# KickerBoard6B.net
KiCad netlist of a schematic drawn in EAGLE
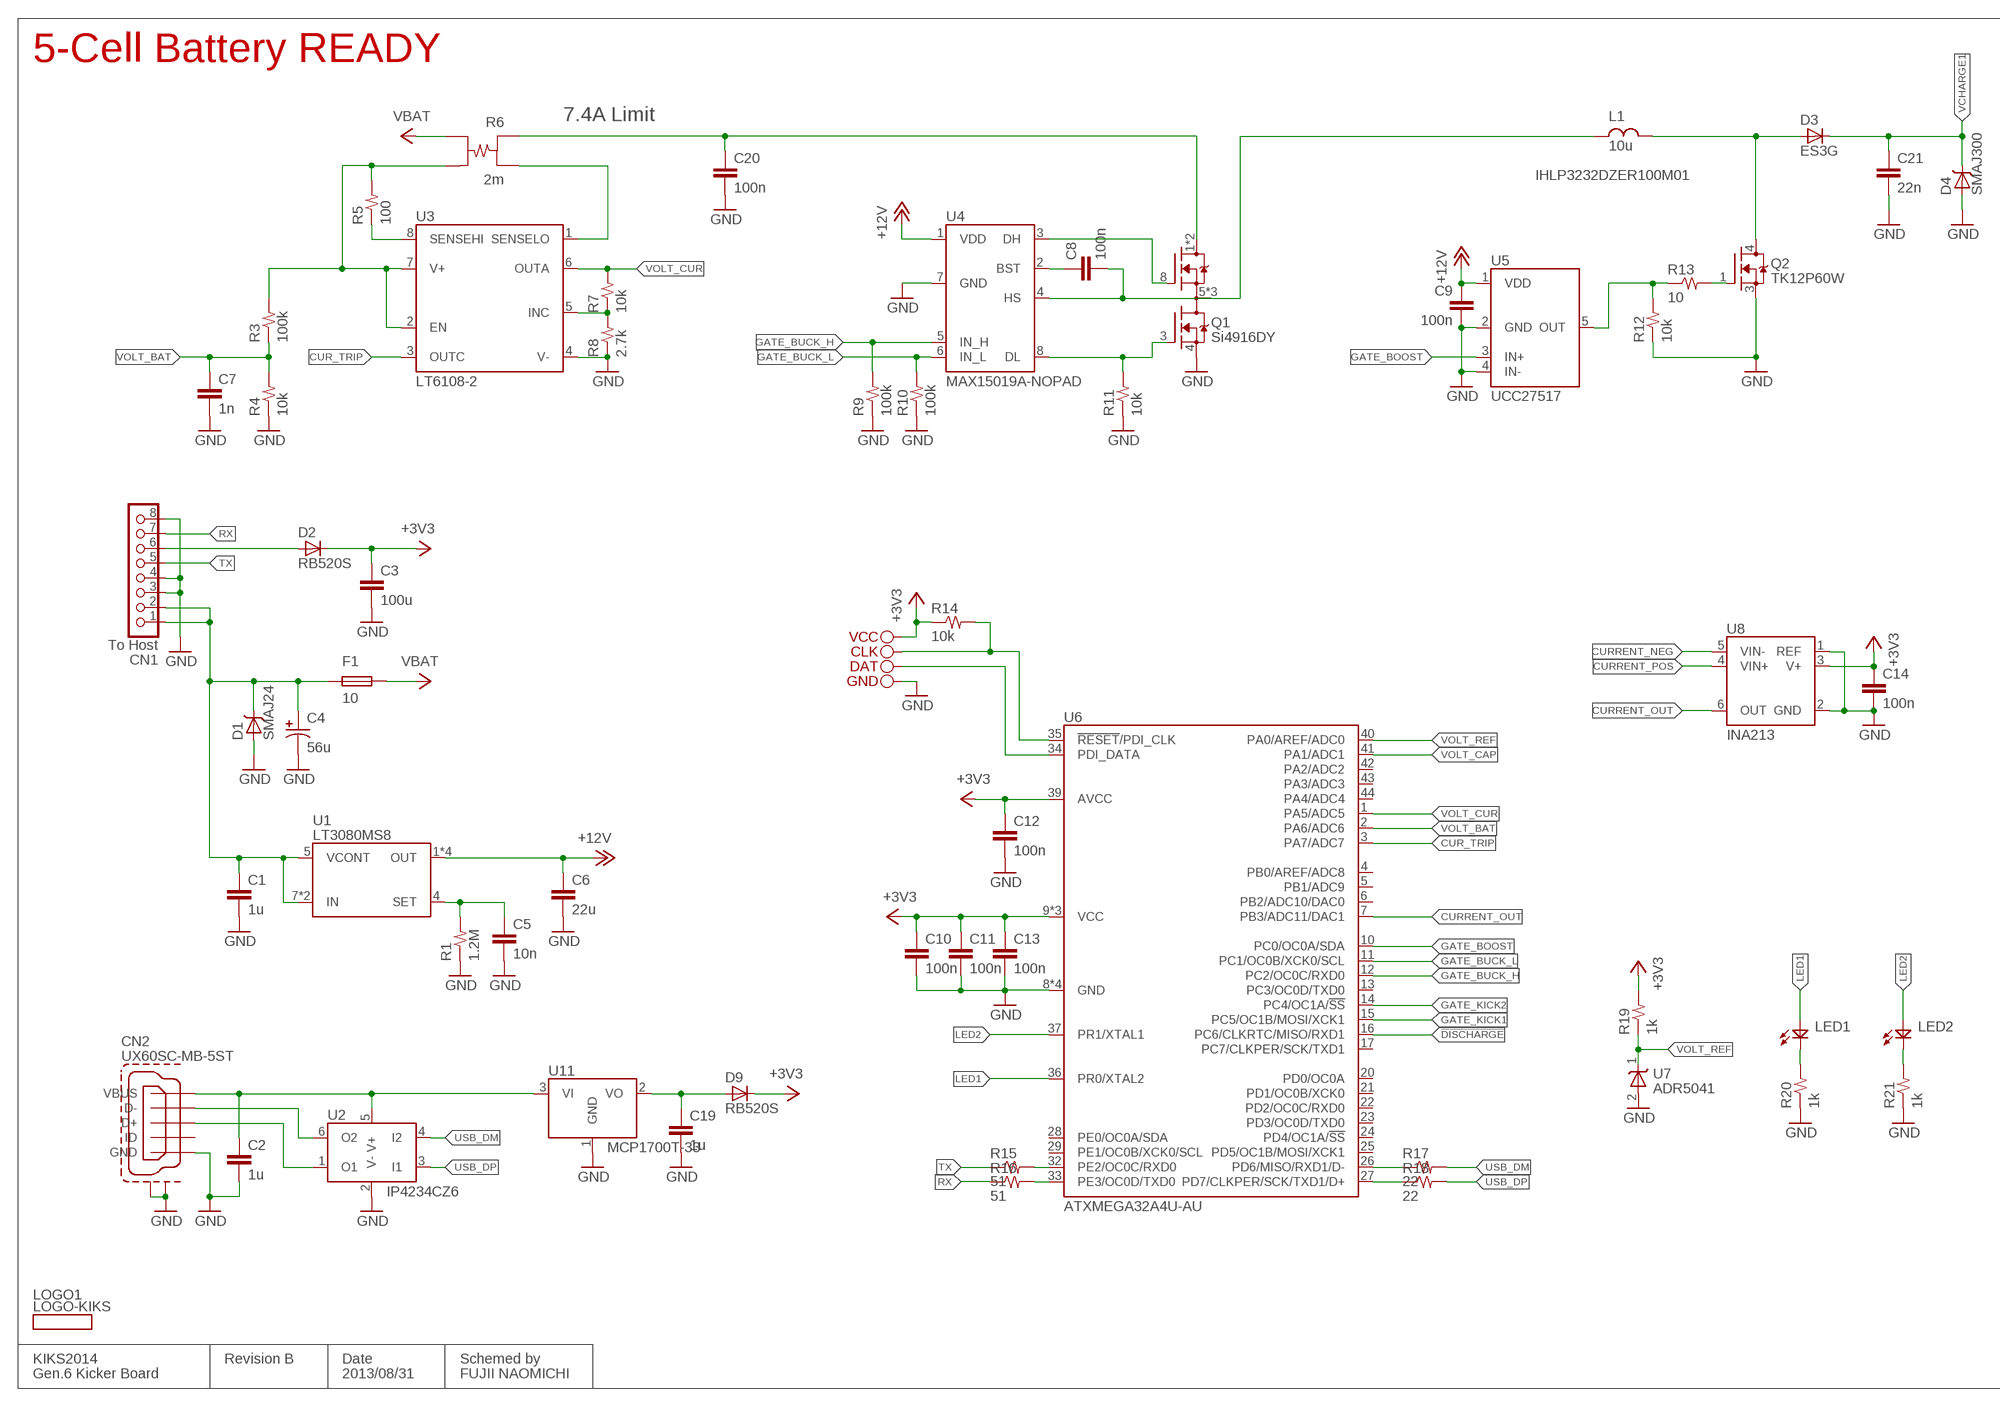
[diagram p0: schematic, sheet 1, part 1 of 2]
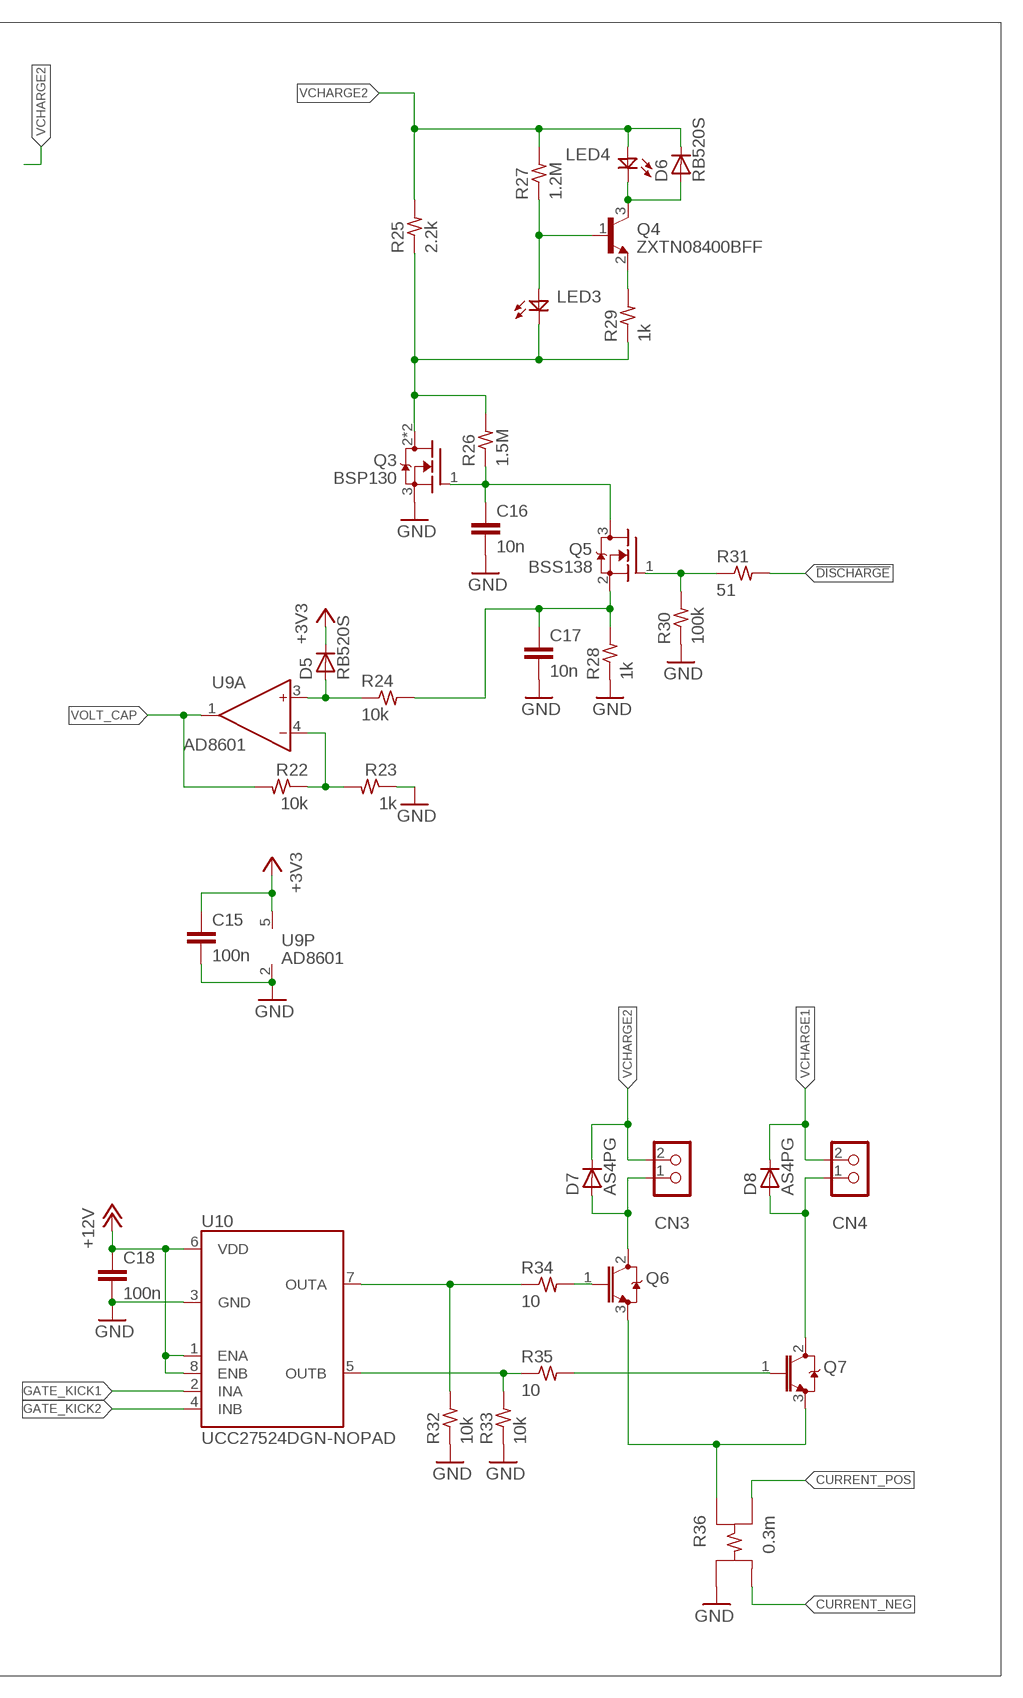
[diagram p1: schematic, sheet 1, part 2 of 2]

(export (version "E")
  (design (tool "Eeschema 10.0.6"))
  (components
    (comp (ref "C1")
      (value "1u")
      (footprint "eagle-import:1608")
      (libsource (lib "eagle-import") (part "C1608"))
    )
    (comp (ref "C2")
      (value "1u")
      (footprint "eagle-import:1005")
      (libsource (lib "eagle-import") (part "C1005"))
    )
    (comp (ref "C3")
      (value "100u")
      (footprint "eagle-import:3225")
      (libsource (lib "eagle-import") (part "C3225"))
    )
    (comp (ref "C4")
      (value "56u")
      (footprint "eagle-import:ES-6.3")
      (libsource (lib "eagle-import") (part "CPOLS-6.3"))
    )
    (comp (ref "C5")
      (value "10n")
      (footprint "eagle-import:1005")
      (libsource (lib "eagle-import") (part "C1005"))
    )
    (comp (ref "C6")
      (value "22u")
      (footprint "eagle-import:3216")
      (libsource (lib "eagle-import") (part "C3216"))
    )
    (comp (ref "C7")
      (value "1n")
      (footprint "eagle-import:1005")
      (libsource (lib "eagle-import") (part "C1005"))
    )
    (comp (ref "C8")
      (value "100n")
      (footprint "eagle-import:1608")
      (libsource (lib "eagle-import") (part "C1608"))
    )
    (comp (ref "C9")
      (value "100n")
      (footprint "eagle-import:1608")
      (libsource (lib "eagle-import") (part "C1608"))
    )
    (comp (ref "C10")
      (value "100n")
      (footprint "eagle-import:1005")
      (libsource (lib "eagle-import") (part "C1005"))
    )
    (comp (ref "C11")
      (value "100n")
      (footprint "eagle-import:1005")
      (libsource (lib "eagle-import") (part "C1005"))
    )
    (comp (ref "C12")
      (value "100n")
      (footprint "eagle-import:1005")
      (libsource (lib "eagle-import") (part "C1005"))
    )
    (comp (ref "C13")
      (value "100n")
      (footprint "eagle-import:1005")
      (libsource (lib "eagle-import") (part "C1005"))
    )
    (comp (ref "C14")
      (value "100n")
      (footprint "eagle-import:1005")
      (libsource (lib "eagle-import") (part "C1005"))
    )
    (comp (ref "C15")
      (value "100n")
      (footprint "eagle-import:1005")
      (libsource (lib "eagle-import") (part "C1005"))
    )
    (comp (ref "C16")
      (value "10n")
      (footprint "eagle-import:1005")
      (libsource (lib "eagle-import") (part "C1005"))
    )
    (comp (ref "C17")
      (value "10n")
      (footprint "eagle-import:1005")
      (libsource (lib "eagle-import") (part "C1005"))
    )
    (comp (ref "C18")
      (value "100n")
      (footprint "eagle-import:1608")
      (libsource (lib "eagle-import") (part "C1608"))
    )
    (comp (ref "C19")
      (value "1u")
      (footprint "eagle-import:1005")
      (libsource (lib "eagle-import") (part "C1005"))
    )
    (comp (ref "C20")
      (value "100n")
      (footprint "eagle-import:1608")
      (libsource (lib "eagle-import") (part "C1608"))
    )
    (comp (ref "C21")
      (value "22n")
      (footprint "eagle-import:3216")
      (libsource (lib "eagle-import") (part "C3216"))
    )
    (comp (ref "CN1")
      (value "To Host")
      (footprint "eagle-import:43650-0800")
      (libsource (lib "eagle-import") (part "43650-0800"))
    )
    (comp (ref "CN2")
      (value "UX60SC-MB-5ST")
      (footprint "eagle-import:UX60SC-MB-5ST")
      (libsource (lib "eagle-import") (part "UX60SC-MB-5ST"))
    )
    (comp (ref "CN3")
      (value "5569-02A2")
      (footprint "eagle-import:5569-02A2")
      (libsource (lib "eagle-import") (part "5569-02A2"))
    )
    (comp (ref "CN4")
      (value "5569-02A2")
      (footprint "eagle-import:5569-02A2")
      (libsource (lib "eagle-import") (part "5569-02A2"))
    )
    (comp (ref "D1")
      (value "SMAJ24")
      (footprint "eagle-import:DO-214AC")
      (libsource (lib "eagle-import") (part "ZENER-DO-214AC"))
    )
    (comp (ref "D2")
      (value "RB520S")
      (footprint "eagle-import:1608")
      (libsource (lib "eagle-import") (part "DIODE-1608"))
    )
    (comp (ref "D3")
      (value "ES3G")
      (footprint "eagle-import:DO-214AB")
      (libsource (lib "eagle-import") (part "DIODE-DO-214AB"))
    )
    (comp (ref "D4")
      (value "SMAJ300")
      (footprint "eagle-import:DO-214AC")
      (libsource (lib "eagle-import") (part "ZENER-DO-214AC"))
    )
    (comp (ref "D5")
      (value "RB520S")
      (footprint "eagle-import:1608")
      (libsource (lib "eagle-import") (part "DIODE-1608"))
    )
    (comp (ref "D6")
      (value "RB520S")
      (footprint "eagle-import:1608")
      (libsource (lib "eagle-import") (part "DIODE-1608"))
    )
    (comp (ref "D7")
      (value "AS4PG")
      (footprint "eagle-import:SMPC")
      (libsource (lib "eagle-import") (part "DIODE-SMPC"))
    )
    (comp (ref "D8")
      (value "AS4PG")
      (footprint "eagle-import:SMPC")
      (libsource (lib "eagle-import") (part "DIODE-SMPC"))
    )
    (comp (ref "D9")
      (value "RB520S")
      (footprint "eagle-import:1608")
      (libsource (lib "eagle-import") (part "DIODE-1608"))
    )
    (comp (ref "F1")
      (value "10")
      (footprint "eagle-import:3216")
      (libsource (lib "eagle-import") (part "F3216"))
    )
    (comp (ref "L1")
      (value "10u")
      (footprint "eagle-import:L8682")
      (libsource (lib "eagle-import") (part "L8682"))
    )
    (comp (ref "LED1")
      (value "LED1611R")
      (footprint "eagle-import:1611")
      (libsource (lib "eagle-import") (part "LED1611R"))
    )
    (comp (ref "LED2")
      (value "LED1611R")
      (footprint "eagle-import:1611")
      (libsource (lib "eagle-import") (part "LED1611R"))
    )
    (comp (ref "LED3")
      (value "LED1608")
      (footprint "eagle-import:1608")
      (libsource (lib "eagle-import") (part "LED1608"))
    )
    (comp (ref "LED4")
      (value "LED1608")
      (footprint "eagle-import:1608")
      (libsource (lib "eagle-import") (part "LED1608"))
    )
    (comp (ref "LOGO1")
      (value "LOGO-KIKS")
      (footprint "eagle-import:LOGO-KIKS")
      (libsource (lib "eagle-import") (part "LOGO-KIKS"))
    )
    (comp (ref "P1")
      (value "VCC")
      (footprint "eagle-import:PAD")
      (libsource (lib "eagle-import") (part "PAD"))
    )
    (comp (ref "P2")
      (value "CLK")
      (footprint "eagle-import:PAD")
      (libsource (lib "eagle-import") (part "PAD"))
    )
    (comp (ref "P3")
      (value "DAT")
      (footprint "eagle-import:PAD")
      (libsource (lib "eagle-import") (part "PAD"))
    )
    (comp (ref "P4")
      (value "GND")
      (footprint "eagle-import:PAD")
      (libsource (lib "eagle-import") (part "PAD"))
    )
    (comp (ref "Q1")
      (value "Si4916DY")
      (footprint "eagle-import:SOP8")
      (libsource (lib "eagle-import") (part "MOS-2N-BRIDGE-SOP8"))
    )
    (comp (ref "Q2")
      (value "TK12P60W")
      (footprint "eagle-import:DPAK-3")
      (libsource (lib "eagle-import") (part "MOS-N-DPAK"))
    )
    (comp (ref "Q3")
      (value "BSP130")
      (footprint "eagle-import:SOT223")
      (libsource (lib "eagle-import") (part "MOS-N-SOT223"))
    )
    (comp (ref "Q4")
      (value "ZXTN08400BFF")
      (footprint "eagle-import:SOT23-3")
      (libsource (lib "eagle-import") (part "NPN-SOT23"))
    )
    (comp (ref "Q5")
      (value "BSS138")
      (footprint "eagle-import:SOT23-3")
      (libsource (lib "eagle-import") (part "MOS-N-SOT23"))
    )
    (comp (ref "Q6")
      (value "IGBT-1N")
      (footprint "eagle-import:TO-247AD_X1")
      (libsource (lib "eagle-import") (part "IGBT-1N"))
    )
    (comp (ref "Q7")
      (value "IGBT-1N")
      (footprint "eagle-import:TO-247AD_X1")
      (libsource (lib "eagle-import") (part "IGBT-1N"))
    )
    (comp (ref "R1")
      (value "1.2M")
      (footprint "eagle-import:1608")
      (libsource (lib "eagle-import") (part "R1608"))
    )
    (comp (ref "R3")
      (value "100k")
      (footprint "eagle-import:1608")
      (libsource (lib "eagle-import") (part "R1608"))
    )
    (comp (ref "R4")
      (value "10k")
      (footprint "eagle-import:1608")
      (libsource (lib "eagle-import") (part "R1608"))
    )
    (comp (ref "R5")
      (value "100")
      (footprint "eagle-import:1608")
      (libsource (lib "eagle-import") (part "R1608"))
    )
    (comp (ref "R6")
      (value "2m")
      (footprint "eagle-import:FC4L")
      (libsource (lib "eagle-import") (part "FC4L"))
    )
    (comp (ref "R7")
      (value "10k")
      (footprint "eagle-import:1608")
      (libsource (lib "eagle-import") (part "R1608"))
    )
    (comp (ref "R8")
      (value "2.7k")
      (footprint "eagle-import:1608")
      (libsource (lib "eagle-import") (part "R1608"))
    )
    (comp (ref "R9")
      (value "100k")
      (footprint "eagle-import:1005")
      (libsource (lib "eagle-import") (part "R1005"))
    )
    (comp (ref "R10")
      (value "100k")
      (footprint "eagle-import:1005")
      (libsource (lib "eagle-import") (part "R1005"))
    )
    (comp (ref "R11")
      (value "10k")
      (footprint "eagle-import:1005")
      (libsource (lib "eagle-import") (part "R1005"))
    )
    (comp (ref "R12")
      (value "10k")
      (footprint "eagle-import:1005")
      (libsource (lib "eagle-import") (part "R1005"))
    )
    (comp (ref "R13")
      (value "10")
      (footprint "eagle-import:2012")
      (libsource (lib "eagle-import") (part "R2012"))
    )
    (comp (ref "R14")
      (value "10k")
      (footprint "eagle-import:1005")
      (libsource (lib "eagle-import") (part "R1005"))
    )
    (comp (ref "R15")
      (value "51")
      (footprint "eagle-import:1005")
      (libsource (lib "eagle-import") (part "R1005"))
    )
    (comp (ref "R16")
      (value "51")
      (footprint "eagle-import:1005")
      (libsource (lib "eagle-import") (part "R1005"))
    )
    (comp (ref "R17")
      (value "22")
      (footprint "eagle-import:1005")
      (libsource (lib "eagle-import") (part "R1005"))
    )
    (comp (ref "R18")
      (value "22")
      (footprint "eagle-import:1005")
      (libsource (lib "eagle-import") (part "R1005"))
    )
    (comp (ref "R19")
      (value "1k")
      (footprint "eagle-import:1005")
      (libsource (lib "eagle-import") (part "R1005"))
    )
    (comp (ref "R20")
      (value "1k")
      (footprint "eagle-import:1005")
      (libsource (lib "eagle-import") (part "R1005"))
    )
    (comp (ref "R21")
      (value "1k")
      (footprint "eagle-import:1005")
      (libsource (lib "eagle-import") (part "R1005"))
    )
    (comp (ref "R22")
      (value "10k")
      (footprint "eagle-import:1608")
      (libsource (lib "eagle-import") (part "R1608"))
    )
    (comp (ref "R23")
      (value "1k")
      (footprint "eagle-import:1608")
      (libsource (lib "eagle-import") (part "R1608"))
    )
    (comp (ref "R24")
      (value "10k")
      (footprint "eagle-import:1005")
      (libsource (lib "eagle-import") (part "R1005"))
    )
    (comp (ref "R25")
      (value "2.2k")
      (footprint "eagle-import:RIEDON-S-3")
      (libsource (lib "eagle-import") (part "R-S-3"))
    )
    (comp (ref "R26")
      (value "1.5M")
      (footprint "eagle-import:1608")
      (libsource (lib "eagle-import") (part "R1608"))
    )
    (comp (ref "R27")
      (value "1.2M")
      (footprint "eagle-import:1608")
      (libsource (lib "eagle-import") (part "R1608"))
    )
    (comp (ref "R28")
      (value "1k")
      (footprint "eagle-import:1608")
      (libsource (lib "eagle-import") (part "R1608"))
    )
    (comp (ref "R29")
      (value "1k")
      (footprint "eagle-import:1005")
      (libsource (lib "eagle-import") (part "R1005"))
    )
    (comp (ref "R30")
      (value "100k")
      (footprint "eagle-import:1005")
      (libsource (lib "eagle-import") (part "R1005"))
    )
    (comp (ref "R31")
      (value "51")
      (footprint "eagle-import:1005")
      (libsource (lib "eagle-import") (part "R1005"))
    )
    (comp (ref "R32")
      (value "10k")
      (footprint "eagle-import:1005")
      (libsource (lib "eagle-import") (part "R1005"))
    )
    (comp (ref "R33")
      (value "10k")
      (footprint "eagle-import:1005")
      (libsource (lib "eagle-import") (part "R1005"))
    )
    (comp (ref "R34")
      (value "10")
      (footprint "eagle-import:2012")
      (libsource (lib "eagle-import") (part "R2012"))
    )
    (comp (ref "R35")
      (value "10")
      (footprint "eagle-import:2012")
      (libsource (lib "eagle-import") (part "R2012"))
    )
    (comp (ref "R36")
      (value "0.3m")
      (footprint "eagle-import:WSL4026")
      (libsource (lib "eagle-import") (part "R4-WSL4026"))
    )
    (comp (ref "U1")
      (value "LT3080MS8")
      (footprint "eagle-import:MSOP8-PAD")
      (libsource (lib "eagle-import") (part "LT3080MS8"))
    )
    (comp (ref "U2")
      (value "IP4234CZ6")
      (footprint "eagle-import:SOT23-6")
      (libsource (lib "eagle-import") (part "TPD2S017"))
    )
    (comp (ref "U3")
      (value "LT6108-2")
      (footprint "eagle-import:MSOP8")
      (libsource (lib "eagle-import") (part "LT6108-2"))
    )
    (comp (ref "U4")
      (value "MAX15019A-NOPAD")
      (footprint "eagle-import:SOP8")
      (libsource (lib "eagle-import") (part "MAX1501A-NOPAD9"))
    )
    (comp (ref "U5")
      (value "UCC27517")
      (footprint "eagle-import:SOT23-5")
      (libsource (lib "eagle-import") (part "UCC27517"))
    )
    (comp (ref "U6")
      (value "ATXMEGA32A4U-AU")
      (footprint "eagle-import:QFP44-0.8")
      (libsource (lib "eagle-import") (part "ATXMEGAA4U-AU32"))
    )
    (comp (ref "U7")
      (value "ADR5041")
      (footprint "eagle-import:SC70-3")
      (libsource (lib "eagle-import") (part "ADR5041"))
    )
    (comp (ref "U8")
      (value "INA213")
      (footprint "eagle-import:SC70-6")
      (libsource (lib "eagle-import") (part "INA213"))
    )
    (comp (ref "U9")
      (value "AD8601")
      (footprint "eagle-import:SOT23-5")
      (libsource (lib "eagle-import") (part "SINGLE-OPAMP-ISO-SOT23"))
    )
    (comp (ref "U10")
      (value "UCC27524DGN-NOPAD")
      (footprint "eagle-import:MSOP8")
      (libsource (lib "eagle-import") (part "UCC27524DGN-NOPAD"))
    )
    (comp (ref "U11")
      (value "MCP1700T-33")
      (footprint "eagle-import:SOT23-3")
      (libsource (lib "eagle-import") (part "MCP1700T-33"))
    )
  )
  (nets
    (net (code "1") (name "+3V3") (class "Default")
      (node (ref "C10") (pin "1") (pinfunction "1_1") (pintype "passive"))
      (node (ref "C11") (pin "1") (pinfunction "1_1") (pintype "passive"))
      (node (ref "C12") (pin "1") (pinfunction "1_1") (pintype "passive"))
      (node (ref "C13") (pin "1") (pinfunction "1_1") (pintype "passive"))
      (node (ref "C14") (pin "1") (pinfunction "1_1") (pintype "passive"))
      (node (ref "C15") (pin "1") (pinfunction "1_1") (pintype "passive"))
      (node (ref "C3") (pin "1") (pinfunction "1_1") (pintype "passive"))
      (node (ref "D2") (pin "K") (pinfunction "K_K") (pintype "passive"))
      (node (ref "D5") (pin "K") (pinfunction "K_K") (pintype "passive"))
      (node (ref "D9") (pin "K") (pinfunction "K_K") (pintype "passive"))
      (node (ref "P1") (pin "1") (pinfunction "P$1_1") (pintype "passive"))
      (node (ref "R14") (pin "1") (pinfunction "1_1") (pintype "passive"))
      (node (ref "R19") (pin "2") (pinfunction "2_2") (pintype "passive"))
      (node (ref "U6") (pin "19") (pinfunction "VCC_19") (pintype "bidirectional"))
      (node (ref "U6") (pin "31") (pinfunction "VCC_31") (pintype "bidirectional"))
      (node (ref "U6") (pin "39") (pinfunction "AVCC_39") (pintype "bidirectional"))
      (node (ref "U6") (pin "9") (pinfunction "VCC_9") (pintype "bidirectional"))
      (node (ref "U8") (pin "3") (pinfunction "V+_3") (pintype "input"))
      (node (ref "U9") (pin "5") (pinfunction "V+_5") (pintype "input"))
    )
    (net (code "2") (name "+12V") (class "Default")
      (node (ref "C18") (pin "1") (pinfunction "1_1") (pintype "passive"))
      (node (ref "C6") (pin "1") (pinfunction "1_1") (pintype "passive"))
      (node (ref "C9") (pin "1") (pinfunction "1_1") (pintype "passive"))
      (node (ref "U1") (pin "1") (pinfunction "OUT_1") (pintype "bidirectional"))
      (node (ref "U1") (pin "2") (pinfunction "OUT_2") (pintype "bidirectional"))
      (node (ref "U1") (pin "3") (pinfunction "OUT_3") (pintype "bidirectional"))
      (node (ref "U1") (pin "PAD") (pinfunction "OUT_PAD") (pintype "bidirectional"))
      (node (ref "U10") (pin "1") (pinfunction "ENA_1") (pintype "bidirectional"))
      (node (ref "U10") (pin "6") (pinfunction "VDD_6") (pintype "bidirectional"))
      (node (ref "U10") (pin "8") (pinfunction "ENB_8") (pintype "bidirectional"))
      (node (ref "U4") (pin "1") (pinfunction "VDD_1") (pintype "input"))
      (node (ref "U5") (pin "1") (pinfunction "VDD_1") (pintype "bidirectional"))
    )
    (net (code "3") (name "/~{DISCHARGE}") (class "Default")
      (node (ref "R31") (pin "2") (pinfunction "2_2") (pintype "passive"))
      (node (ref "U6") (pin "16") (pinfunction "PC6/CLKRTC/MISO/RXD1_16") (pintype "bidirectional"))
    )
    (net (code "4") (name "CURRENT_NEG") (class "Default")
      (node (ref "R36") (pin "I2") (pinfunction "I2_I2") (pintype "passive"))
      (node (ref "U8") (pin "5") (pinfunction "VIN-_5") (pintype "input"))
    )
    (net (code "5") (name "CURRENT_OUT") (class "Default")
      (node (ref "U6") (pin "7") (pinfunction "PB3/ADC11/DAC1_7") (pintype "bidirectional"))
      (node (ref "U8") (pin "6") (pinfunction "OUT_6") (pintype "output"))
    )
    (net (code "6") (name "CURRENT_POS") (class "Default")
      (node (ref "R36") (pin "I1") (pinfunction "I1_I1") (pintype "passive"))
      (node (ref "U8") (pin "4") (pinfunction "VIN+_4") (pintype "input"))
    )
    (net (code "7") (name "CUR_TRIP") (class "Default")
      (node (ref "U3") (pin "3") (pinfunction "OUTC_3") (pintype "bidirectional"))
      (node (ref "U6") (pin "3") (pinfunction "PA7/ADC7_3") (pintype "bidirectional"))
    )
    (net (code "8") (name "GATE_BOOST") (class "Default")
      (node (ref "U5") (pin "3") (pinfunction "IN+_3") (pintype "bidirectional"))
      (node (ref "U6") (pin "10") (pinfunction "PC0/OC0A/SDA_10") (pintype "bidirectional"))
    )
    (net (code "9") (name "GATE_BUCK_H") (class "Default")
      (node (ref "R9") (pin "2") (pinfunction "2_2") (pintype "passive"))
      (node (ref "U4") (pin "5") (pinfunction "IN_H_5") (pintype "input"))
      (node (ref "U6") (pin "12") (pinfunction "PC2/OC0C/RXD0_12") (pintype "bidirectional"))
    )
    (net (code "10") (name "GATE_BUCK_L") (class "Default")
      (node (ref "R10") (pin "2") (pinfunction "2_2") (pintype "passive"))
      (node (ref "U4") (pin "6") (pinfunction "IN_L_6") (pintype "input"))
      (node (ref "U6") (pin "11") (pinfunction "PC1/OC0B/XCK0/SCL_11") (pintype "bidirectional"))
    )
    (net (code "11") (name "GATE_KICK1") (class "Default")
      (node (ref "U10") (pin "2") (pinfunction "INA_2") (pintype "bidirectional"))
      (node (ref "U6") (pin "15") (pinfunction "PC5/OC1B/MOSI/XCK1_15") (pintype "bidirectional"))
    )
    (net (code "12") (name "GATE_KICK2") (class "Default")
      (node (ref "U10") (pin "4") (pinfunction "INB_4") (pintype "bidirectional"))
      (node (ref "U6") (pin "14") (pinfunction "PC4/OC1A/~{SS}_14") (pintype "bidirectional"))
    )
    (net (code "13") (name "GND") (class "Default")
      (node (ref "C1") (pin "2") (pinfunction "2_2") (pintype "passive"))
      (node (ref "C10") (pin "2") (pinfunction "2_2") (pintype "passive"))
      (node (ref "C11") (pin "2") (pinfunction "2_2") (pintype "passive"))
      (node (ref "C12") (pin "2") (pinfunction "2_2") (pintype "passive"))
      (node (ref "C13") (pin "2") (pinfunction "2_2") (pintype "passive"))
      (node (ref "C14") (pin "2") (pinfunction "2_2") (pintype "passive"))
      (node (ref "C15") (pin "2") (pinfunction "2_2") (pintype "passive"))
      (node (ref "C16") (pin "2") (pinfunction "2_2") (pintype "passive"))
      (node (ref "C17") (pin "2") (pinfunction "2_2") (pintype "passive"))
      (node (ref "C18") (pin "2") (pinfunction "2_2") (pintype "passive"))
      (node (ref "C19") (pin "2") (pinfunction "2_2") (pintype "passive"))
      (node (ref "C2") (pin "2") (pinfunction "2_2") (pintype "passive"))
      (node (ref "C20") (pin "2") (pinfunction "2_2") (pintype "passive"))
      (node (ref "C21") (pin "2") (pinfunction "2_2") (pintype "passive"))
      (node (ref "C3") (pin "2") (pinfunction "2_2") (pintype "passive"))
      (node (ref "C4") (pin "N") (pinfunction "N_N") (pintype "passive"))
      (node (ref "C5") (pin "2") (pinfunction "2_2") (pintype "passive"))
      (node (ref "C6") (pin "2") (pinfunction "2_2") (pintype "passive"))
      (node (ref "C7") (pin "2") (pinfunction "2_2") (pintype "passive"))
      (node (ref "C9") (pin "2") (pinfunction "2_2") (pintype "passive"))
      (node (ref "CN1") (pin "3") (pinfunction "3_3") (pintype "passive"))
      (node (ref "CN1") (pin "4") (pinfunction "4_4") (pintype "passive"))
      (node (ref "CN1") (pin "8") (pinfunction "8_8") (pintype "passive"))
      (node (ref "CN2") (pin "5") (pinfunction "GND_5") (pintype "passive"))
      (node (ref "CN2") (pin "S1") (pinfunction "S1_S1") (pintype "passive"))
      (node (ref "CN2") (pin "S2") (pinfunction "S2_S2") (pintype "passive"))
      (node (ref "D1") (pin "A") (pinfunction "A_A") (pintype "passive"))
      (node (ref "D4") (pin "A") (pinfunction "A_A") (pintype "passive"))
      (node (ref "P4") (pin "1") (pinfunction "P$1_1") (pintype "passive"))
      (node (ref "Q1") (pin "4") (pinfunction "S2_4") (pintype "passive"))
      (node (ref "Q2") (pin "3") (pinfunction "S_3") (pintype "passive"))
      (node (ref "Q3") (pin "3") (pinfunction "S_3") (pintype "passive"))
      (node (ref "R1") (pin "1") (pinfunction "1_1") (pintype "passive"))
      (node (ref "R10") (pin "1") (pinfunction "1_1") (pintype "passive"))
      (node (ref "R11") (pin "1") (pinfunction "1_1") (pintype "passive"))
      (node (ref "R12") (pin "1") (pinfunction "1_1") (pintype "passive"))
      (node (ref "R20") (pin "1") (pinfunction "1_1") (pintype "passive"))
      (node (ref "R21") (pin "1") (pinfunction "1_1") (pintype "passive"))
      (node (ref "R23") (pin "1") (pinfunction "1_1") (pintype "passive"))
      (node (ref "R28") (pin "1") (pinfunction "1_1") (pintype "passive"))
      (node (ref "R30") (pin "1") (pinfunction "1_1") (pintype "passive"))
      (node (ref "R32") (pin "1") (pinfunction "1_1") (pintype "passive"))
      (node (ref "R33") (pin "1") (pinfunction "1_1") (pintype "passive"))
      (node (ref "R36") (pin "V2") (pinfunction "V2_V2") (pintype "passive"))
      (node (ref "R4") (pin "1") (pinfunction "1_1") (pintype "passive"))
      (node (ref "R8") (pin "1") (pinfunction "1_1") (pintype "passive"))
      (node (ref "R9") (pin "1") (pinfunction "1_1") (pintype "passive"))
      (node (ref "U10") (pin "3") (pinfunction "GND_3") (pintype "bidirectional"))
      (node (ref "U11") (pin "1") (pinfunction "GND_1") (pintype "bidirectional"))
      (node (ref "U2") (pin "2") (pinfunction "V-_2") (pintype "bidirectional"))
      (node (ref "U3") (pin "4") (pinfunction "V-_4") (pintype "bidirectional"))
      (node (ref "U4") (pin "7") (pinfunction "GND_7") (pintype "input"))
      (node (ref "U5") (pin "2") (pinfunction "GND_2") (pintype "bidirectional"))
      (node (ref "U5") (pin "4") (pinfunction "IN-_4") (pintype "bidirectional"))
      (node (ref "U6") (pin "18") (pinfunction "GND_18") (pintype "bidirectional"))
      (node (ref "U6") (pin "30") (pinfunction "GND_30") (pintype "bidirectional"))
      (node (ref "U6") (pin "38") (pinfunction "GND_38") (pintype "bidirectional"))
      (node (ref "U6") (pin "8") (pinfunction "GND_8") (pintype "bidirectional"))
      (node (ref "U7") (pin "2") (pinfunction "A_2") (pintype "passive"))
      (node (ref "U8") (pin "1") (pinfunction "REF_1") (pintype "input"))
      (node (ref "U8") (pin "2") (pinfunction "GND_2") (pintype "input"))
      (node (ref "U9") (pin "2") (pinfunction "V-_2") (pintype "input"))
    )
    (net (code "14") (name "LED1") (class "Default")
      (node (ref "LED1") (pin "A") (pinfunction "A_A") (pintype "passive"))
      (node (ref "U6") (pin "36") (pinfunction "PR0/XTAL2_36") (pintype "bidirectional"))
    )
    (net (code "15") (name "LED2") (class "Default")
      (node (ref "LED2") (pin "A") (pinfunction "A_A") (pintype "passive"))
      (node (ref "U6") (pin "37") (pinfunction "PR1/XTAL1_37") (pintype "bidirectional"))
    )
    (net (code "16") (name "Net-(C20-Pad1)") (class "Default")
      (node (ref "C20") (pin "1") (pinfunction "1_1") (pintype "passive"))
      (node (ref "Q1") (pin "1") (pinfunction "D1_1") (pintype "passive"))
      (node (ref "Q1") (pin "2") (pinfunction "D1_2") (pintype "passive"))
      (node (ref "R6") (pin "V1") (pinfunction "V1_V1") (pintype "passive"))
    )
    (net (code "17") (name "Net-(CN1-Pad6)") (class "Default")
      (node (ref "CN1") (pin "6") (pinfunction "6_6") (pintype "passive"))
      (node (ref "D2") (pin "A") (pinfunction "A_A") (pintype "passive"))
    )
    (net (code "18") (name "Net-(CN2-D+)") (class "Default")
      (node (ref "CN2") (pin "3") (pinfunction "D+_3") (pintype "passive"))
      (node (ref "U2") (pin "1") (pinfunction "O1_1") (pintype "bidirectional"))
    )
    (net (code "19") (name "Net-(CN2-D-)") (class "Default")
      (node (ref "CN2") (pin "2") (pinfunction "D-_2") (pintype "passive"))
      (node (ref "U2") (pin "6") (pinfunction "O2_6") (pintype "bidirectional"))
    )
    (net (code "20") (name "Net-(CN2-VBUS)") (class "Default")
      (node (ref "C2") (pin "1") (pinfunction "1_1") (pintype "passive"))
      (node (ref "CN2") (pin "1") (pinfunction "VBUS_1") (pintype "passive"))
      (node (ref "U11") (pin "3") (pinfunction "VI_3") (pintype "bidirectional"))
      (node (ref "U2") (pin "5") (pinfunction "V+_5") (pintype "bidirectional"))
    )
    (net (code "21") (name "Net-(LED1-PadK)") (class "Default")
      (node (ref "LED1") (pin "K") (pinfunction "K_K") (pintype "passive"))
      (node (ref "R20") (pin "2") (pinfunction "2_2") (pintype "passive"))
    )
    (net (code "22") (name "Net-(LED2-PadK)") (class "Default")
      (node (ref "LED2") (pin "K") (pinfunction "K_K") (pintype "passive"))
      (node (ref "R21") (pin "2") (pinfunction "2_2") (pintype "passive"))
    )
    (net (code "23") (name "Net-(LED3-PadK)") (class "Default")
      (node (ref "LED3") (pin "K") (pinfunction "K_K") (pintype "passive"))
      (node (ref "Q3") (pin "2") (pinfunction "D_2") (pintype "passive"))
      (node (ref "Q3") (pin "4") (pinfunction "D_4") (pintype "passive"))
      (node (ref "R25") (pin "1") (pinfunction "1_1") (pintype "passive"))
      (node (ref "R26") (pin "2") (pinfunction "2_2") (pintype "passive"))
      (node (ref "R29") (pin "1") (pinfunction "1_1") (pintype "passive"))
    )
    (net (code "24") (name "Net-(P2-P$1)") (class "Default")
      (node (ref "P2") (pin "1") (pinfunction "P$1_1") (pintype "passive"))
      (node (ref "R14") (pin "2") (pinfunction "2_2") (pintype "passive"))
      (node (ref "U6") (pin "35") (pinfunction "~{RESET}/PDI_CLK_35") (pintype "bidirectional"))
    )
    (net (code "25") (name "Net-(P3-P$1)") (class "Default")
      (node (ref "P3") (pin "1") (pinfunction "P$1_1") (pintype "passive"))
      (node (ref "U6") (pin "34") (pinfunction "PDI_DATA_34") (pintype "bidirectional"))
    )
    (net (code "26") (name "Net-(Q1-G1)") (class "Default")
      (node (ref "Q1") (pin "8") (pinfunction "G1_8") (pintype "passive"))
      (node (ref "U4") (pin "3") (pinfunction "DH_3") (pintype "output"))
    )
    (net (code "27") (name "Net-(Q1-G2)") (class "Default")
      (node (ref "Q1") (pin "3") (pinfunction "G2_3") (pintype "passive"))
      (node (ref "R11") (pin "2") (pinfunction "2_2") (pintype "passive"))
      (node (ref "U4") (pin "8") (pinfunction "DL_8") (pintype "output"))
    )
    (net (code "28") (name "Net-(Q2-D)") (class "Default")
      (node (ref "D3") (pin "A") (pinfunction "A_A") (pintype "passive"))
      (node (ref "L1") (pin "2") (pinfunction "2_2") (pintype "passive"))
      (node (ref "Q2") (pin "4") (pinfunction "D_4") (pintype "passive"))
    )
    (net (code "29") (name "Net-(Q2-G)") (class "Default")
      (node (ref "Q2") (pin "1") (pinfunction "G_1") (pintype "passive"))
      (node (ref "R13") (pin "2") (pinfunction "2_2") (pintype "passive"))
    )
    (net (code "30") (name "Net-(Q3-G)") (class "Default")
      (node (ref "C16") (pin "1") (pinfunction "1_1") (pintype "passive"))
      (node (ref "Q3") (pin "1") (pinfunction "G_1") (pintype "passive"))
      (node (ref "Q5") (pin "3") (pinfunction "D_3") (pintype "passive"))
      (node (ref "R26") (pin "1") (pinfunction "1_1") (pintype "passive"))
    )
    (net (code "31") (name "Net-(Q4-B)") (class "Default")
      (node (ref "LED3") (pin "A") (pinfunction "A_A") (pintype "passive"))
      (node (ref "Q4") (pin "1") (pinfunction "B_1") (pintype "passive"))
      (node (ref "R27") (pin "1") (pinfunction "1_1") (pintype "passive"))
    )
    (net (code "32") (name "Net-(Q4-C)") (class "Default")
      (node (ref "D6") (pin "A") (pinfunction "A_A") (pintype "passive"))
      (node (ref "LED4") (pin "K") (pinfunction "K_K") (pintype "passive"))
      (node (ref "Q4") (pin "3") (pinfunction "C_3") (pintype "passive"))
    )
    (net (code "33") (name "Net-(Q4-E)") (class "Default")
      (node (ref "Q4") (pin "2") (pinfunction "E_2") (pintype "passive"))
      (node (ref "R29") (pin "2") (pinfunction "2_2") (pintype "passive"))
    )
    (net (code "34") (name "Net-(Q5-G)") (class "Default")
      (node (ref "Q5") (pin "1") (pinfunction "G_1") (pintype "passive"))
      (node (ref "R30") (pin "2") (pinfunction "2_2") (pintype "passive"))
      (node (ref "R31") (pin "1") (pinfunction "1_1") (pintype "passive"))
    )
    (net (code "35") (name "Net-(Q5-S)") (class "Default")
      (node (ref "C17") (pin "1") (pinfunction "1_1") (pintype "passive"))
      (node (ref "Q5") (pin "2") (pinfunction "S_2") (pintype "passive"))
      (node (ref "R24") (pin "2") (pinfunction "2_2") (pintype "passive"))
      (node (ref "R28") (pin "2") (pinfunction "2_2") (pintype "passive"))
    )
    (net (code "36") (name "Net-(Q6-C)") (class "Default")
      (node (ref "CN3") (pin "1") (pinfunction "1_1") (pintype "passive"))
      (node (ref "D7") (pin "1") (pinfunction "A_1") (pintype "passive"))
      (node (ref "D7") (pin "2") (pinfunction "A_2") (pintype "passive"))
      (node (ref "Q6") (pin "2") (pinfunction "C_2") (pintype "passive"))
    )
    (net (code "37") (name "Net-(Q6-E)") (class "Default")
      (node (ref "Q6") (pin "3") (pinfunction "E_3") (pintype "passive"))
      (node (ref "Q7") (pin "3") (pinfunction "E_3") (pintype "passive"))
      (node (ref "R36") (pin "V1") (pinfunction "V1_V1") (pintype "passive"))
    )
    (net (code "38") (name "Net-(Q6-G)") (class "Default")
      (node (ref "Q6") (pin "1") (pinfunction "G_1") (pintype "passive"))
      (node (ref "R34") (pin "2") (pinfunction "2_2") (pintype "passive"))
    )
    (net (code "39") (name "Net-(Q7-C)") (class "Default")
      (node (ref "CN4") (pin "1") (pinfunction "1_1") (pintype "passive"))
      (node (ref "D8") (pin "1") (pinfunction "A_1") (pintype "passive"))
      (node (ref "D8") (pin "2") (pinfunction "A_2") (pintype "passive"))
      (node (ref "Q7") (pin "2") (pinfunction "C_2") (pintype "passive"))
    )
    (net (code "40") (name "Net-(Q7-G)") (class "Default")
      (node (ref "Q7") (pin "1") (pinfunction "G_1") (pintype "passive"))
      (node (ref "R35") (pin "2") (pinfunction "2_2") (pintype "passive"))
    )
    (net (code "41") (name "Net-(U1-SET)") (class "Default")
      (node (ref "C5") (pin "1") (pinfunction "1_1") (pintype "passive"))
      (node (ref "R1") (pin "2") (pinfunction "2_2") (pintype "passive"))
      (node (ref "U1") (pin "4") (pinfunction "SET_4") (pintype "bidirectional"))
    )
    (net (code "42") (name "Net-(U1-VCONT)") (class "Default")
      (node (ref "C1") (pin "1") (pinfunction "1_1") (pintype "passive"))
      (node (ref "C4") (pin "P") (pinfunction "P_P") (pintype "passive"))
      (node (ref "CN1") (pin "1") (pinfunction "1_1") (pintype "passive"))
      (node (ref "CN1") (pin "2") (pinfunction "2_2") (pintype "passive"))
      (node (ref "D1") (pin "K") (pinfunction "K_K") (pintype "passive"))
      (node (ref "F1") (pin "1") (pinfunction "1_1") (pintype "passive"))
      (node (ref "U1") (pin "5") (pinfunction "VCONT_5") (pintype "bidirectional"))
      (node (ref "U1") (pin "7") (pinfunction "IN_7") (pintype "bidirectional"))
      (node (ref "U1") (pin "8") (pinfunction "IN_8") (pintype "bidirectional"))
    )
    (net (code "43") (name "Net-(U3-EN)") (class "Default")
      (node (ref "R3") (pin "2") (pinfunction "2_2") (pintype "passive"))
      (node (ref "R5") (pin "2") (pinfunction "2_2") (pintype "passive"))
      (node (ref "R6") (pin "I2") (pinfunction "I2_I2") (pintype "passive"))
      (node (ref "U3") (pin "2") (pinfunction "EN_2") (pintype "bidirectional"))
      (node (ref "U3") (pin "7") (pinfunction "V+_7") (pintype "bidirectional"))
    )
    (net (code "44") (name "Net-(U3-INC)") (class "Default")
      (node (ref "R7") (pin "1") (pinfunction "1_1") (pintype "passive"))
      (node (ref "R8") (pin "2") (pinfunction "2_2") (pintype "passive"))
      (node (ref "U3") (pin "5") (pinfunction "INC_5") (pintype "bidirectional"))
    )
    (net (code "45") (name "Net-(U3-SENSEHI)") (class "Default")
      (node (ref "R5") (pin "1") (pinfunction "1_1") (pintype "passive"))
      (node (ref "U3") (pin "8") (pinfunction "SENSEHI_8") (pintype "bidirectional"))
    )
    (net (code "46") (name "Net-(U3-SENSELO)") (class "Default")
      (node (ref "R6") (pin "I1") (pinfunction "I1_I1") (pintype "passive"))
      (node (ref "U3") (pin "1") (pinfunction "SENSELO_1") (pintype "bidirectional"))
    )
    (net (code "47") (name "Net-(U4-BST)") (class "Default")
      (node (ref "C8") (pin "1") (pinfunction "1_1") (pintype "passive"))
      (node (ref "U4") (pin "2") (pinfunction "BST_2") (pintype "output"))
    )
    (net (code "48") (name "Net-(U4-HS)") (class "Default")
      (node (ref "C8") (pin "2") (pinfunction "2_2") (pintype "passive"))
      (node (ref "L1") (pin "1") (pinfunction "1_1") (pintype "passive"))
      (node (ref "Q1") (pin "5") (pinfunction "S1_D2_5") (pintype "passive"))
      (node (ref "Q1") (pin "6") (pinfunction "S1_D2_6") (pintype "passive"))
      (node (ref "Q1") (pin "7") (pinfunction "S1_D2_7") (pintype "passive"))
      (node (ref "U4") (pin "4") (pinfunction "HS_4") (pintype "input"))
    )
    (net (code "49") (name "Net-(U5-OUT)") (class "Default")
      (node (ref "R12") (pin "2") (pinfunction "2_2") (pintype "passive"))
      (node (ref "R13") (pin "1") (pinfunction "1_1") (pintype "passive"))
      (node (ref "U5") (pin "5") (pinfunction "OUT_5") (pintype "bidirectional"))
    )
    (net (code "50") (name "Net-(U6-PD6{slash}MISO{slash}RXD1{slash}D-)") (class "Default")
      (node (ref "R17") (pin "1") (pinfunction "1_1") (pintype "passive"))
      (node (ref "U6") (pin "26") (pinfunction "PD6/MISO/RXD1/D-_26") (pintype "bidirectional"))
    )
    (net (code "51") (name "Net-(U6-PD7{slash}CLKPER{slash}SCK{slash}TXD1{slash}D+)") (class "Default")
      (node (ref "R18") (pin "1") (pinfunction "1_1") (pintype "passive"))
      (node (ref "U6") (pin "27") (pinfunction "PD7/CLKPER/SCK/TXD1/D+_27") (pintype "bidirectional"))
    )
    (net (code "52") (name "Net-(U6-PE2{slash}OC0C{slash}RXD0)") (class "Default")
      (node (ref "R15") (pin "2") (pinfunction "2_2") (pintype "passive"))
      (node (ref "U6") (pin "32") (pinfunction "PE2/OC0C/RXD0_32") (pintype "bidirectional"))
    )
    (net (code "53") (name "Net-(U6-PE3{slash}OC0D{slash}TXD0)") (class "Default")
      (node (ref "R16") (pin "2") (pinfunction "2_2") (pintype "passive"))
      (node (ref "U6") (pin "33") (pinfunction "PE3/OC0D/TXD0_33") (pintype "bidirectional"))
    )
    (net (code "54") (name "Net-(U9A-IN+)") (class "Default")
      (node (ref "D5") (pin "A") (pinfunction "A_A") (pintype "passive"))
      (node (ref "R24") (pin "1") (pinfunction "1_1") (pintype "passive"))
      (node (ref "U9") (pin "3") (pinfunction "IN+_3") (pintype "input"))
    )
    (net (code "55") (name "Net-(U9A-IN-)") (class "Default")
      (node (ref "R22") (pin "1") (pinfunction "1_1") (pintype "passive"))
      (node (ref "R23") (pin "2") (pinfunction "2_2") (pintype "passive"))
      (node (ref "U9") (pin "4") (pinfunction "IN-_4") (pintype "input"))
    )
    (net (code "56") (name "Net-(U10-OUTA)") (class "Default")
      (node (ref "R32") (pin "2") (pinfunction "2_2") (pintype "passive"))
      (node (ref "R34") (pin "1") (pinfunction "1_1") (pintype "passive"))
      (node (ref "U10") (pin "7") (pinfunction "OUTA_7") (pintype "bidirectional"))
    )
    (net (code "57") (name "Net-(U10-OUTB)") (class "Default")
      (node (ref "R33") (pin "2") (pinfunction "2_2") (pintype "passive"))
      (node (ref "R35") (pin "1") (pinfunction "1_1") (pintype "passive"))
      (node (ref "U10") (pin "5") (pinfunction "OUTB_5") (pintype "bidirectional"))
    )
    (net (code "58") (name "Net-(U11-VO)") (class "Default")
      (node (ref "C19") (pin "1") (pinfunction "1_1") (pintype "passive"))
      (node (ref "D9") (pin "A") (pinfunction "A_A") (pintype "passive"))
      (node (ref "U11") (pin "2") (pinfunction "VO_2") (pintype "bidirectional"))
    )
    (net (code "59") (name "RX") (class "Default")
      (node (ref "CN1") (pin "7") (pinfunction "7_7") (pintype "passive"))
      (node (ref "R16") (pin "1") (pinfunction "1_1") (pintype "passive"))
    )
    (net (code "60") (name "TX") (class "Default")
      (node (ref "CN1") (pin "5") (pinfunction "5_5") (pintype "passive"))
      (node (ref "R15") (pin "1") (pinfunction "1_1") (pintype "passive"))
    )
    (net (code "61") (name "USB_DM") (class "Default")
      (node (ref "R17") (pin "2") (pinfunction "2_2") (pintype "passive"))
      (node (ref "U2") (pin "4") (pinfunction "I2_4") (pintype "bidirectional"))
    )
    (net (code "62") (name "USB_DP") (class "Default")
      (node (ref "R18") (pin "2") (pinfunction "2_2") (pintype "passive"))
      (node (ref "U2") (pin "3") (pinfunction "I1_3") (pintype "bidirectional"))
    )
    (net (code "63") (name "VBAT") (class "Default")
      (node (ref "F1") (pin "2") (pinfunction "2_2") (pintype "passive"))
      (node (ref "R6") (pin "V2") (pinfunction "V2_V2") (pintype "passive"))
    )
    (net (code "64") (name "VCHARGE1") (class "Default")
      (node (ref "C21") (pin "1") (pinfunction "1_1") (pintype "passive"))
      (node (ref "CN4") (pin "2") (pinfunction "2_2") (pintype "passive"))
      (node (ref "D3") (pin "K") (pinfunction "K_K") (pintype "passive"))
      (node (ref "D4") (pin "K") (pinfunction "K_K") (pintype "passive"))
      (node (ref "D8") (pin "K") (pinfunction "K_K") (pintype "passive"))
    )
    (net (code "65") (name "VCHARGE2") (class "Default")
      (node (ref "CN3") (pin "2") (pinfunction "2_2") (pintype "passive"))
      (node (ref "D6") (pin "K") (pinfunction "K_K") (pintype "passive"))
      (node (ref "D7") (pin "K") (pinfunction "K_K") (pintype "passive"))
      (node (ref "LED4") (pin "A") (pinfunction "A_A") (pintype "passive"))
      (node (ref "R25") (pin "2") (pinfunction "2_2") (pintype "passive"))
      (node (ref "R27") (pin "2") (pinfunction "2_2") (pintype "passive"))
    )
    (net (code "66") (name "VOLT_BAT") (class "Default")
      (node (ref "C7") (pin "1") (pinfunction "1_1") (pintype "passive"))
      (node (ref "R3") (pin "1") (pinfunction "1_1") (pintype "passive"))
      (node (ref "R4") (pin "2") (pinfunction "2_2") (pintype "passive"))
      (node (ref "U6") (pin "2") (pinfunction "PA6/ADC6_2") (pintype "bidirectional"))
    )
    (net (code "67") (name "VOLT_CAP") (class "Default")
      (node (ref "R22") (pin "2") (pinfunction "2_2") (pintype "passive"))
      (node (ref "U6") (pin "41") (pinfunction "PA1/ADC1_41") (pintype "bidirectional"))
      (node (ref "U9") (pin "1") (pinfunction "OUT_1") (pintype "output"))
    )
    (net (code "68") (name "VOLT_CUR") (class "Default")
      (node (ref "R7") (pin "2") (pinfunction "2_2") (pintype "passive"))
      (node (ref "U3") (pin "6") (pinfunction "OUTA_6") (pintype "bidirectional"))
      (node (ref "U6") (pin "1") (pinfunction "PA5/ADC5_1") (pintype "bidirectional"))
    )
    (net (code "69") (name "VOLT_REF") (class "Default")
      (node (ref "R19") (pin "1") (pinfunction "1_1") (pintype "passive"))
      (node (ref "U6") (pin "40") (pinfunction "PA0/AREF/ADC0_40") (pintype "bidirectional"))
      (node (ref "U7") (pin "1") (pinfunction "K_1") (pintype "passive"))
    )
    (net (code "70") (name "unconnected-(CN2-ID-Pad4)") (class "Default")
      (node (ref "CN2") (pin "4") (pinfunction "ID_4") (pintype "passive"))
    )
    (net (code "71") (name "unconnected-(U6-PA2{slash}ADC2-Pad42)") (class "Default")
      (node (ref "U6") (pin "42") (pinfunction "PA2/ADC2_42") (pintype "bidirectional"))
    )
    (net (code "72") (name "unconnected-(U6-PA3{slash}ADC3-Pad43)") (class "Default")
      (node (ref "U6") (pin "43") (pinfunction "PA3/ADC3_43") (pintype "bidirectional"))
    )
    (net (code "73") (name "unconnected-(U6-PA4{slash}ADC4-Pad44)") (class "Default")
      (node (ref "U6") (pin "44") (pinfunction "PA4/ADC4_44") (pintype "bidirectional"))
    )
    (net (code "74") (name "unconnected-(U6-PB0{slash}AREF{slash}ADC8-Pad4)") (class "Default")
      (node (ref "U6") (pin "4") (pinfunction "PB0/AREF/ADC8_4") (pintype "bidirectional"))
    )
    (net (code "75") (name "unconnected-(U6-PB1{slash}ADC9-Pad5)") (class "Default")
      (node (ref "U6") (pin "5") (pinfunction "PB1/ADC9_5") (pintype "bidirectional"))
    )
    (net (code "76") (name "unconnected-(U6-PB2{slash}ADC10{slash}DAC0-Pad6)") (class "Default")
      (node (ref "U6") (pin "6") (pinfunction "PB2/ADC10/DAC0_6") (pintype "bidirectional"))
    )
    (net (code "77") (name "unconnected-(U6-PC3{slash}OC0D{slash}TXD0-Pad13)") (class "Default")
      (node (ref "U6") (pin "13") (pinfunction "PC3/OC0D/TXD0_13") (pintype "bidirectional"))
    )
    (net (code "78") (name "unconnected-(U6-PC7{slash}CLKPER{slash}SCK{slash}TXD1-Pad17)") (class "Default")
      (node (ref "U6") (pin "17") (pinfunction "PC7/CLKPER/SCK/TXD1_17") (pintype "bidirectional"))
    )
    (net (code "79") (name "unconnected-(U6-PD0{slash}OC0A-Pad20)") (class "Default")
      (node (ref "U6") (pin "20") (pinfunction "PD0/OC0A_20") (pintype "bidirectional"))
    )
    (net (code "80") (name "unconnected-(U6-PD1{slash}OC0B{slash}XCK0-Pad21)") (class "Default")
      (node (ref "U6") (pin "21") (pinfunction "PD1/OC0B/XCK0_21") (pintype "bidirectional"))
    )
    (net (code "81") (name "unconnected-(U6-PD2{slash}OC0C{slash}RXD0-Pad22)") (class "Default")
      (node (ref "U6") (pin "22") (pinfunction "PD2/OC0C/RXD0_22") (pintype "bidirectional"))
    )
    (net (code "82") (name "unconnected-(U6-PD3{slash}OC0D{slash}TXD0-Pad23)") (class "Default")
      (node (ref "U6") (pin "23") (pinfunction "PD3/OC0D/TXD0_23") (pintype "bidirectional"))
    )
    (net (code "83") (name "unconnected-(U6-PD4{slash}OC1A{slash}~{SS}-Pad24)") (class "Default")
      (node (ref "U6") (pin "24") (pinfunction "PD4/OC1A/~{SS}_24") (pintype "bidirectional"))
    )
    (net (code "84") (name "unconnected-(U6-PD5{slash}OC1B{slash}MOSI{slash}XCK1-Pad25)") (class "Default")
      (node (ref "U6") (pin "25") (pinfunction "PD5/OC1B/MOSI/XCK1_25") (pintype "bidirectional"))
    )
    (net (code "85") (name "unconnected-(U6-PE0{slash}OC0A{slash}SDA-Pad28)") (class "Default")
      (node (ref "U6") (pin "28") (pinfunction "PE0/OC0A/SDA_28") (pintype "bidirectional"))
    )
    (net (code "86") (name "unconnected-(U6-PE1{slash}OC0B{slash}XCK0{slash}SCL-Pad29)") (class "Default")
      (node (ref "U6") (pin "29") (pinfunction "PE1/OC0B/XCK0/SCL_29") (pintype "bidirectional"))
    )
  )
)
